# matrix_4x4.net
KiCad netlist of a schematic drawn in EAGLE
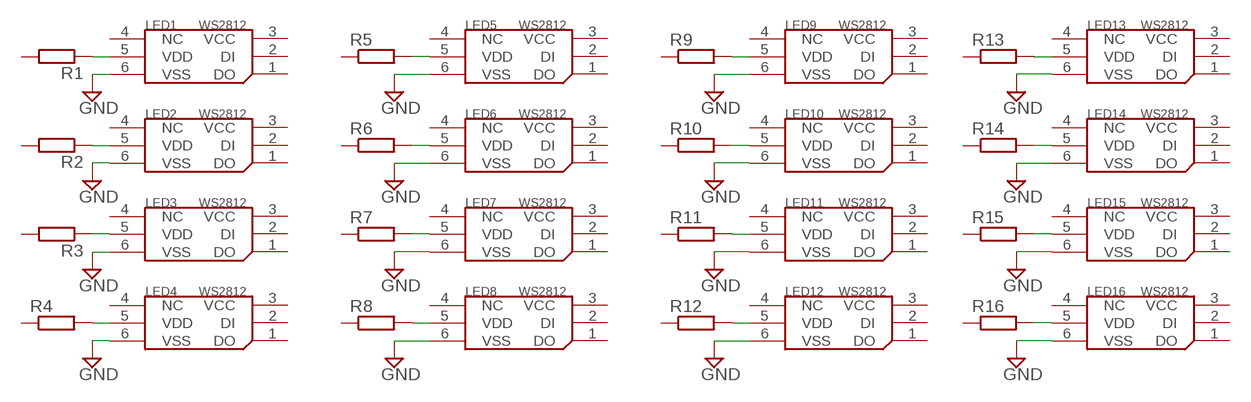
[diagram p0: schematic, sheet 1]

(export (version "E")
  (design (tool "Eeschema 10.0.6"))
  (components
    (comp (ref "LED1")
      (value "WS2812")
      (footprint "eagle-import:LED6-SMD-5050")
      (libsource (lib "eagle-import") (part "WS2812"))
    )
    (comp (ref "LED2")
      (value "WS2812")
      (footprint "eagle-import:LED6-SMD-5050")
      (libsource (lib "eagle-import") (part "WS2812"))
    )
    (comp (ref "LED3")
      (value "WS2812")
      (footprint "eagle-import:LED6-SMD-5050")
      (libsource (lib "eagle-import") (part "WS2812"))
    )
    (comp (ref "LED4")
      (value "WS2812")
      (footprint "eagle-import:LED6-SMD-5050")
      (libsource (lib "eagle-import") (part "WS2812"))
    )
    (comp (ref "LED5")
      (value "WS2812")
      (footprint "eagle-import:LED6-SMD-5050")
      (libsource (lib "eagle-import") (part "WS2812"))
    )
    (comp (ref "LED6")
      (value "WS2812")
      (footprint "eagle-import:LED6-SMD-5050")
      (libsource (lib "eagle-import") (part "WS2812"))
    )
    (comp (ref "LED7")
      (value "WS2812")
      (footprint "eagle-import:LED6-SMD-5050")
      (libsource (lib "eagle-import") (part "WS2812"))
    )
    (comp (ref "LED8")
      (value "WS2812")
      (footprint "eagle-import:LED6-SMD-5050")
      (libsource (lib "eagle-import") (part "WS2812"))
    )
    (comp (ref "LED9")
      (value "WS2812")
      (footprint "eagle-import:LED6-SMD-5050")
      (libsource (lib "eagle-import") (part "WS2812"))
    )
    (comp (ref "LED10")
      (value "WS2812")
      (footprint "eagle-import:LED6-SMD-5050")
      (libsource (lib "eagle-import") (part "WS2812"))
    )
    (comp (ref "LED11")
      (value "WS2812")
      (footprint "eagle-import:LED6-SMD-5050")
      (libsource (lib "eagle-import") (part "WS2812"))
    )
    (comp (ref "LED12")
      (value "WS2812")
      (footprint "eagle-import:LED6-SMD-5050")
      (libsource (lib "eagle-import") (part "WS2812"))
    )
    (comp (ref "LED13")
      (value "WS2812")
      (footprint "eagle-import:LED6-SMD-5050")
      (libsource (lib "eagle-import") (part "WS2812"))
    )
    (comp (ref "LED14")
      (value "WS2812")
      (footprint "eagle-import:LED6-SMD-5050")
      (libsource (lib "eagle-import") (part "WS2812"))
    )
    (comp (ref "LED15")
      (value "WS2812")
      (footprint "eagle-import:LED6-SMD-5050")
      (libsource (lib "eagle-import") (part "WS2812"))
    )
    (comp (ref "LED16")
      (value "WS2812")
      (footprint "eagle-import:LED6-SMD-5050")
      (libsource (lib "eagle-import") (part "WS2812"))
    )
    (comp (ref "R1")
      (value "R-EU_M0805")
      (footprint "eagle-import:M0805")
      (libsource (lib "eagle-import") (part "R-EU_M0805"))
    )
    (comp (ref "R2")
      (value "R-EU_M0805")
      (footprint "eagle-import:M0805")
      (libsource (lib "eagle-import") (part "R-EU_M0805"))
    )
    (comp (ref "R3")
      (value "R-EU_M0805")
      (footprint "eagle-import:M0805")
      (libsource (lib "eagle-import") (part "R-EU_M0805"))
    )
    (comp (ref "R4")
      (value "R-EU_M0805")
      (footprint "eagle-import:M0805")
      (libsource (lib "eagle-import") (part "R-EU_M0805"))
    )
    (comp (ref "R5")
      (value "R-EU_M0805")
      (footprint "eagle-import:M0805")
      (libsource (lib "eagle-import") (part "R-EU_M0805"))
    )
    (comp (ref "R6")
      (value "R-EU_M0805")
      (footprint "eagle-import:M0805")
      (libsource (lib "eagle-import") (part "R-EU_M0805"))
    )
    (comp (ref "R7")
      (value "R-EU_M0805")
      (footprint "eagle-import:M0805")
      (libsource (lib "eagle-import") (part "R-EU_M0805"))
    )
    (comp (ref "R8")
      (value "R-EU_M0805")
      (footprint "eagle-import:M0805")
      (libsource (lib "eagle-import") (part "R-EU_M0805"))
    )
    (comp (ref "R9")
      (value "R-EU_M0805")
      (footprint "eagle-import:M0805")
      (libsource (lib "eagle-import") (part "R-EU_M0805"))
    )
    (comp (ref "R10")
      (value "R-EU_M0805")
      (footprint "eagle-import:M0805")
      (libsource (lib "eagle-import") (part "R-EU_M0805"))
    )
    (comp (ref "R11")
      (value "R-EU_M0805")
      (footprint "eagle-import:M0805")
      (libsource (lib "eagle-import") (part "R-EU_M0805"))
    )
    (comp (ref "R12")
      (value "R-EU_M0805")
      (footprint "eagle-import:M0805")
      (libsource (lib "eagle-import") (part "R-EU_M0805"))
    )
    (comp (ref "R13")
      (value "R-EU_M0805")
      (footprint "eagle-import:M0805")
      (libsource (lib "eagle-import") (part "R-EU_M0805"))
    )
    (comp (ref "R14")
      (value "R-EU_M0805")
      (footprint "eagle-import:M0805")
      (libsource (lib "eagle-import") (part "R-EU_M0805"))
    )
    (comp (ref "R15")
      (value "R-EU_M0805")
      (footprint "eagle-import:M0805")
      (libsource (lib "eagle-import") (part "R-EU_M0805"))
    )
    (comp (ref "R16")
      (value "R-EU_M0805")
      (footprint "eagle-import:M0805")
      (libsource (lib "eagle-import") (part "R-EU_M0805"))
    )
  )
  (nets
    (net (code "1") (name "GND") (class "Default")
      (node (ref "LED1") (pin "6") (pinfunction "VSS_6") (pintype "bidirectional"))
      (node (ref "LED10") (pin "6") (pinfunction "VSS_6") (pintype "bidirectional"))
      (node (ref "LED11") (pin "6") (pinfunction "VSS_6") (pintype "bidirectional"))
      (node (ref "LED12") (pin "6") (pinfunction "VSS_6") (pintype "bidirectional"))
      (node (ref "LED13") (pin "6") (pinfunction "VSS_6") (pintype "bidirectional"))
      (node (ref "LED14") (pin "6") (pinfunction "VSS_6") (pintype "bidirectional"))
      (node (ref "LED15") (pin "6") (pinfunction "VSS_6") (pintype "bidirectional"))
      (node (ref "LED16") (pin "6") (pinfunction "VSS_6") (pintype "bidirectional"))
      (node (ref "LED2") (pin "6") (pinfunction "VSS_6") (pintype "bidirectional"))
      (node (ref "LED3") (pin "6") (pinfunction "VSS_6") (pintype "bidirectional"))
      (node (ref "LED4") (pin "6") (pinfunction "VSS_6") (pintype "bidirectional"))
      (node (ref "LED5") (pin "6") (pinfunction "VSS_6") (pintype "bidirectional"))
      (node (ref "LED6") (pin "6") (pinfunction "VSS_6") (pintype "bidirectional"))
      (node (ref "LED7") (pin "6") (pinfunction "VSS_6") (pintype "bidirectional"))
      (node (ref "LED8") (pin "6") (pinfunction "VSS_6") (pintype "bidirectional"))
      (node (ref "LED9") (pin "6") (pinfunction "VSS_6") (pintype "bidirectional"))
    )
    (net (code "2") (name "Net-(LED1-VDD)") (class "Default")
      (node (ref "LED1") (pin "5") (pinfunction "VDD_5") (pintype "bidirectional"))
      (node (ref "R1") (pin "1") (pinfunction "1_1") (pintype "passive"))
    )
    (net (code "3") (name "Net-(LED2-VDD)") (class "Default")
      (node (ref "LED2") (pin "5") (pinfunction "VDD_5") (pintype "bidirectional"))
      (node (ref "R2") (pin "1") (pinfunction "1_1") (pintype "passive"))
    )
    (net (code "4") (name "Net-(LED3-VDD)") (class "Default")
      (node (ref "LED3") (pin "5") (pinfunction "VDD_5") (pintype "bidirectional"))
      (node (ref "R3") (pin "1") (pinfunction "1_1") (pintype "passive"))
    )
    (net (code "5") (name "Net-(LED4-VDD)") (class "Default")
      (node (ref "LED4") (pin "5") (pinfunction "VDD_5") (pintype "bidirectional"))
      (node (ref "R4") (pin "2") (pinfunction "2_2") (pintype "passive"))
    )
    (net (code "6") (name "Net-(LED5-VDD)") (class "Default")
      (node (ref "LED5") (pin "5") (pinfunction "VDD_5") (pintype "bidirectional"))
      (node (ref "R5") (pin "2") (pinfunction "2_2") (pintype "passive"))
    )
    (net (code "7") (name "Net-(LED6-VDD)") (class "Default")
      (node (ref "LED6") (pin "5") (pinfunction "VDD_5") (pintype "bidirectional"))
      (node (ref "R6") (pin "2") (pinfunction "2_2") (pintype "passive"))
    )
    (net (code "8") (name "Net-(LED7-VDD)") (class "Default")
      (node (ref "LED7") (pin "5") (pinfunction "VDD_5") (pintype "bidirectional"))
      (node (ref "R7") (pin "2") (pinfunction "2_2") (pintype "passive"))
    )
    (net (code "9") (name "Net-(LED8-VDD)") (class "Default")
      (node (ref "LED8") (pin "5") (pinfunction "VDD_5") (pintype "bidirectional"))
      (node (ref "R8") (pin "2") (pinfunction "2_2") (pintype "passive"))
    )
    (net (code "10") (name "Net-(LED9-VDD)") (class "Default")
      (node (ref "LED9") (pin "5") (pinfunction "VDD_5") (pintype "bidirectional"))
      (node (ref "R9") (pin "2") (pinfunction "2_2") (pintype "passive"))
    )
    (net (code "11") (name "Net-(LED10-VDD)") (class "Default")
      (node (ref "LED10") (pin "5") (pinfunction "VDD_5") (pintype "bidirectional"))
      (node (ref "R10") (pin "2") (pinfunction "2_2") (pintype "passive"))
    )
    (net (code "12") (name "Net-(LED11-VDD)") (class "Default")
      (node (ref "LED11") (pin "5") (pinfunction "VDD_5") (pintype "bidirectional"))
      (node (ref "R11") (pin "2") (pinfunction "2_2") (pintype "passive"))
    )
    (net (code "13") (name "Net-(LED12-VDD)") (class "Default")
      (node (ref "LED12") (pin "5") (pinfunction "VDD_5") (pintype "bidirectional"))
      (node (ref "R12") (pin "2") (pinfunction "2_2") (pintype "passive"))
    )
    (net (code "14") (name "Net-(LED13-VDD)") (class "Default")
      (node (ref "LED13") (pin "5") (pinfunction "VDD_5") (pintype "bidirectional"))
      (node (ref "R13") (pin "2") (pinfunction "2_2") (pintype "passive"))
    )
    (net (code "15") (name "Net-(LED14-VDD)") (class "Default")
      (node (ref "LED14") (pin "5") (pinfunction "VDD_5") (pintype "bidirectional"))
      (node (ref "R14") (pin "2") (pinfunction "2_2") (pintype "passive"))
    )
    (net (code "16") (name "Net-(LED15-VDD)") (class "Default")
      (node (ref "LED15") (pin "5") (pinfunction "VDD_5") (pintype "bidirectional"))
      (node (ref "R15") (pin "2") (pinfunction "2_2") (pintype "passive"))
    )
    (net (code "17") (name "Net-(LED16-VDD)") (class "Default")
      (node (ref "LED16") (pin "5") (pinfunction "VDD_5") (pintype "bidirectional"))
      (node (ref "R16") (pin "2") (pinfunction "2_2") (pintype "passive"))
    )
    (net (code "18") (name "unconnected-(LED1-DI-Pad2)") (class "Default")
      (node (ref "LED1") (pin "2") (pinfunction "DI_2") (pintype "bidirectional"))
    )
    (net (code "19") (name "unconnected-(LED1-DO-Pad1)") (class "Default")
      (node (ref "LED1") (pin "1") (pinfunction "DO_1") (pintype "bidirectional"))
    )
    (net (code "20") (name "unconnected-(LED1-NC-Pad4)") (class "Default")
      (node (ref "LED1") (pin "4") (pinfunction "NC_4") (pintype "bidirectional"))
    )
    (net (code "21") (name "unconnected-(LED1-VCC-Pad3)") (class "Default")
      (node (ref "LED1") (pin "3") (pinfunction "VCC_3") (pintype "bidirectional"))
    )
    (net (code "22") (name "unconnected-(LED2-DI-Pad2)") (class "Default")
      (node (ref "LED2") (pin "2") (pinfunction "DI_2") (pintype "bidirectional"))
    )
    (net (code "23") (name "unconnected-(LED2-DO-Pad1)") (class "Default")
      (node (ref "LED2") (pin "1") (pinfunction "DO_1") (pintype "bidirectional"))
    )
    (net (code "24") (name "unconnected-(LED2-NC-Pad4)") (class "Default")
      (node (ref "LED2") (pin "4") (pinfunction "NC_4") (pintype "bidirectional"))
    )
    (net (code "25") (name "unconnected-(LED2-VCC-Pad3)") (class "Default")
      (node (ref "LED2") (pin "3") (pinfunction "VCC_3") (pintype "bidirectional"))
    )
    (net (code "26") (name "unconnected-(LED3-DI-Pad2)") (class "Default")
      (node (ref "LED3") (pin "2") (pinfunction "DI_2") (pintype "bidirectional"))
    )
    (net (code "27") (name "unconnected-(LED3-DO-Pad1)") (class "Default")
      (node (ref "LED3") (pin "1") (pinfunction "DO_1") (pintype "bidirectional"))
    )
    (net (code "28") (name "unconnected-(LED3-NC-Pad4)") (class "Default")
      (node (ref "LED3") (pin "4") (pinfunction "NC_4") (pintype "bidirectional"))
    )
    (net (code "29") (name "unconnected-(LED3-VCC-Pad3)") (class "Default")
      (node (ref "LED3") (pin "3") (pinfunction "VCC_3") (pintype "bidirectional"))
    )
    (net (code "30") (name "unconnected-(LED4-DI-Pad2)") (class "Default")
      (node (ref "LED4") (pin "2") (pinfunction "DI_2") (pintype "bidirectional"))
    )
    (net (code "31") (name "unconnected-(LED4-DO-Pad1)") (class "Default")
      (node (ref "LED4") (pin "1") (pinfunction "DO_1") (pintype "bidirectional"))
    )
    (net (code "32") (name "unconnected-(LED4-NC-Pad4)") (class "Default")
      (node (ref "LED4") (pin "4") (pinfunction "NC_4") (pintype "bidirectional"))
    )
    (net (code "33") (name "unconnected-(LED4-VCC-Pad3)") (class "Default")
      (node (ref "LED4") (pin "3") (pinfunction "VCC_3") (pintype "bidirectional"))
    )
    (net (code "34") (name "unconnected-(LED5-DI-Pad2)") (class "Default")
      (node (ref "LED5") (pin "2") (pinfunction "DI_2") (pintype "bidirectional"))
    )
    (net (code "35") (name "unconnected-(LED5-DO-Pad1)") (class "Default")
      (node (ref "LED5") (pin "1") (pinfunction "DO_1") (pintype "bidirectional"))
    )
    (net (code "36") (name "unconnected-(LED5-NC-Pad4)") (class "Default")
      (node (ref "LED5") (pin "4") (pinfunction "NC_4") (pintype "bidirectional"))
    )
    (net (code "37") (name "unconnected-(LED5-VCC-Pad3)") (class "Default")
      (node (ref "LED5") (pin "3") (pinfunction "VCC_3") (pintype "bidirectional"))
    )
    (net (code "38") (name "unconnected-(LED6-DI-Pad2)") (class "Default")
      (node (ref "LED6") (pin "2") (pinfunction "DI_2") (pintype "bidirectional"))
    )
    (net (code "39") (name "unconnected-(LED6-DO-Pad1)") (class "Default")
      (node (ref "LED6") (pin "1") (pinfunction "DO_1") (pintype "bidirectional"))
    )
    (net (code "40") (name "unconnected-(LED6-NC-Pad4)") (class "Default")
      (node (ref "LED6") (pin "4") (pinfunction "NC_4") (pintype "bidirectional"))
    )
    (net (code "41") (name "unconnected-(LED6-VCC-Pad3)") (class "Default")
      (node (ref "LED6") (pin "3") (pinfunction "VCC_3") (pintype "bidirectional"))
    )
    (net (code "42") (name "unconnected-(LED7-DI-Pad2)") (class "Default")
      (node (ref "LED7") (pin "2") (pinfunction "DI_2") (pintype "bidirectional"))
    )
    (net (code "43") (name "unconnected-(LED7-DO-Pad1)") (class "Default")
      (node (ref "LED7") (pin "1") (pinfunction "DO_1") (pintype "bidirectional"))
    )
    (net (code "44") (name "unconnected-(LED7-NC-Pad4)") (class "Default")
      (node (ref "LED7") (pin "4") (pinfunction "NC_4") (pintype "bidirectional"))
    )
    (net (code "45") (name "unconnected-(LED7-VCC-Pad3)") (class "Default")
      (node (ref "LED7") (pin "3") (pinfunction "VCC_3") (pintype "bidirectional"))
    )
    (net (code "46") (name "unconnected-(LED8-DI-Pad2)") (class "Default")
      (node (ref "LED8") (pin "2") (pinfunction "DI_2") (pintype "bidirectional"))
    )
    (net (code "47") (name "unconnected-(LED8-DO-Pad1)") (class "Default")
      (node (ref "LED8") (pin "1") (pinfunction "DO_1") (pintype "bidirectional"))
    )
    (net (code "48") (name "unconnected-(LED8-NC-Pad4)") (class "Default")
      (node (ref "LED8") (pin "4") (pinfunction "NC_4") (pintype "bidirectional"))
    )
    (net (code "49") (name "unconnected-(LED8-VCC-Pad3)") (class "Default")
      (node (ref "LED8") (pin "3") (pinfunction "VCC_3") (pintype "bidirectional"))
    )
    (net (code "50") (name "unconnected-(LED9-DI-Pad2)") (class "Default")
      (node (ref "LED9") (pin "2") (pinfunction "DI_2") (pintype "bidirectional"))
    )
    (net (code "51") (name "unconnected-(LED9-DO-Pad1)") (class "Default")
      (node (ref "LED9") (pin "1") (pinfunction "DO_1") (pintype "bidirectional"))
    )
    (net (code "52") (name "unconnected-(LED9-NC-Pad4)") (class "Default")
      (node (ref "LED9") (pin "4") (pinfunction "NC_4") (pintype "bidirectional"))
    )
    (net (code "53") (name "unconnected-(LED9-VCC-Pad3)") (class "Default")
      (node (ref "LED9") (pin "3") (pinfunction "VCC_3") (pintype "bidirectional"))
    )
    (net (code "54") (name "unconnected-(LED10-DI-Pad2)") (class "Default")
      (node (ref "LED10") (pin "2") (pinfunction "DI_2") (pintype "bidirectional"))
    )
    (net (code "55") (name "unconnected-(LED10-DO-Pad1)") (class "Default")
      (node (ref "LED10") (pin "1") (pinfunction "DO_1") (pintype "bidirectional"))
    )
    (net (code "56") (name "unconnected-(LED10-NC-Pad4)") (class "Default")
      (node (ref "LED10") (pin "4") (pinfunction "NC_4") (pintype "bidirectional"))
    )
    (net (code "57") (name "unconnected-(LED10-VCC-Pad3)") (class "Default")
      (node (ref "LED10") (pin "3") (pinfunction "VCC_3") (pintype "bidirectional"))
    )
    (net (code "58") (name "unconnected-(LED11-DI-Pad2)") (class "Default")
      (node (ref "LED11") (pin "2") (pinfunction "DI_2") (pintype "bidirectional"))
    )
    (net (code "59") (name "unconnected-(LED11-DO-Pad1)") (class "Default")
      (node (ref "LED11") (pin "1") (pinfunction "DO_1") (pintype "bidirectional"))
    )
    (net (code "60") (name "unconnected-(LED11-NC-Pad4)") (class "Default")
      (node (ref "LED11") (pin "4") (pinfunction "NC_4") (pintype "bidirectional"))
    )
    (net (code "61") (name "unconnected-(LED11-VCC-Pad3)") (class "Default")
      (node (ref "LED11") (pin "3") (pinfunction "VCC_3") (pintype "bidirectional"))
    )
    (net (code "62") (name "unconnected-(LED12-DI-Pad2)") (class "Default")
      (node (ref "LED12") (pin "2") (pinfunction "DI_2") (pintype "bidirectional"))
    )
    (net (code "63") (name "unconnected-(LED12-DO-Pad1)") (class "Default")
      (node (ref "LED12") (pin "1") (pinfunction "DO_1") (pintype "bidirectional"))
    )
    (net (code "64") (name "unconnected-(LED12-NC-Pad4)") (class "Default")
      (node (ref "LED12") (pin "4") (pinfunction "NC_4") (pintype "bidirectional"))
    )
    (net (code "65") (name "unconnected-(LED12-VCC-Pad3)") (class "Default")
      (node (ref "LED12") (pin "3") (pinfunction "VCC_3") (pintype "bidirectional"))
    )
    (net (code "66") (name "unconnected-(LED13-DI-Pad2)") (class "Default")
      (node (ref "LED13") (pin "2") (pinfunction "DI_2") (pintype "bidirectional"))
    )
    (net (code "67") (name "unconnected-(LED13-DO-Pad1)") (class "Default")
      (node (ref "LED13") (pin "1") (pinfunction "DO_1") (pintype "bidirectional"))
    )
    (net (code "68") (name "unconnected-(LED13-NC-Pad4)") (class "Default")
      (node (ref "LED13") (pin "4") (pinfunction "NC_4") (pintype "bidirectional"))
    )
    (net (code "69") (name "unconnected-(LED13-VCC-Pad3)") (class "Default")
      (node (ref "LED13") (pin "3") (pinfunction "VCC_3") (pintype "bidirectional"))
    )
    (net (code "70") (name "unconnected-(LED14-DI-Pad2)") (class "Default")
      (node (ref "LED14") (pin "2") (pinfunction "DI_2") (pintype "bidirectional"))
    )
    (net (code "71") (name "unconnected-(LED14-DO-Pad1)") (class "Default")
      (node (ref "LED14") (pin "1") (pinfunction "DO_1") (pintype "bidirectional"))
    )
    (net (code "72") (name "unconnected-(LED14-NC-Pad4)") (class "Default")
      (node (ref "LED14") (pin "4") (pinfunction "NC_4") (pintype "bidirectional"))
    )
    (net (code "73") (name "unconnected-(LED14-VCC-Pad3)") (class "Default")
      (node (ref "LED14") (pin "3") (pinfunction "VCC_3") (pintype "bidirectional"))
    )
    (net (code "74") (name "unconnected-(LED15-DI-Pad2)") (class "Default")
      (node (ref "LED15") (pin "2") (pinfunction "DI_2") (pintype "bidirectional"))
    )
    (net (code "75") (name "unconnected-(LED15-DO-Pad1)") (class "Default")
      (node (ref "LED15") (pin "1") (pinfunction "DO_1") (pintype "bidirectional"))
    )
    (net (code "76") (name "unconnected-(LED15-NC-Pad4)") (class "Default")
      (node (ref "LED15") (pin "4") (pinfunction "NC_4") (pintype "bidirectional"))
    )
    (net (code "77") (name "unconnected-(LED15-VCC-Pad3)") (class "Default")
      (node (ref "LED15") (pin "3") (pinfunction "VCC_3") (pintype "bidirectional"))
    )
    (net (code "78") (name "unconnected-(LED16-DI-Pad2)") (class "Default")
      (node (ref "LED16") (pin "2") (pinfunction "DI_2") (pintype "bidirectional"))
    )
    (net (code "79") (name "unconnected-(LED16-DO-Pad1)") (class "Default")
      (node (ref "LED16") (pin "1") (pinfunction "DO_1") (pintype "bidirectional"))
    )
    (net (code "80") (name "unconnected-(LED16-NC-Pad4)") (class "Default")
      (node (ref "LED16") (pin "4") (pinfunction "NC_4") (pintype "bidirectional"))
    )
    (net (code "81") (name "unconnected-(LED16-VCC-Pad3)") (class "Default")
      (node (ref "LED16") (pin "3") (pinfunction "VCC_3") (pintype "bidirectional"))
    )
    (net (code "82") (name "unconnected-(R1-Pad2)") (class "Default")
      (node (ref "R1") (pin "2") (pinfunction "2_2") (pintype "passive"))
    )
    (net (code "83") (name "unconnected-(R2-Pad2)") (class "Default")
      (node (ref "R2") (pin "2") (pinfunction "2_2") (pintype "passive"))
    )
    (net (code "84") (name "unconnected-(R3-Pad2)") (class "Default")
      (node (ref "R3") (pin "2") (pinfunction "2_2") (pintype "passive"))
    )
    (net (code "85") (name "unconnected-(R4-Pad1)") (class "Default")
      (node (ref "R4") (pin "1") (pinfunction "1_1") (pintype "passive"))
    )
    (net (code "86") (name "unconnected-(R5-Pad1)") (class "Default")
      (node (ref "R5") (pin "1") (pinfunction "1_1") (pintype "passive"))
    )
    (net (code "87") (name "unconnected-(R6-Pad1)") (class "Default")
      (node (ref "R6") (pin "1") (pinfunction "1_1") (pintype "passive"))
    )
    (net (code "88") (name "unconnected-(R7-Pad1)") (class "Default")
      (node (ref "R7") (pin "1") (pinfunction "1_1") (pintype "passive"))
    )
    (net (code "89") (name "unconnected-(R8-Pad1)") (class "Default")
      (node (ref "R8") (pin "1") (pinfunction "1_1") (pintype "passive"))
    )
    (net (code "90") (name "unconnected-(R9-Pad1)") (class "Default")
      (node (ref "R9") (pin "1") (pinfunction "1_1") (pintype "passive"))
    )
    (net (code "91") (name "unconnected-(R10-Pad1)") (class "Default")
      (node (ref "R10") (pin "1") (pinfunction "1_1") (pintype "passive"))
    )
    (net (code "92") (name "unconnected-(R11-Pad1)") (class "Default")
      (node (ref "R11") (pin "1") (pinfunction "1_1") (pintype "passive"))
    )
    (net (code "93") (name "unconnected-(R12-Pad1)") (class "Default")
      (node (ref "R12") (pin "1") (pinfunction "1_1") (pintype "passive"))
    )
    (net (code "94") (name "unconnected-(R13-Pad1)") (class "Default")
      (node (ref "R13") (pin "1") (pinfunction "1_1") (pintype "passive"))
    )
    (net (code "95") (name "unconnected-(R14-Pad1)") (class "Default")
      (node (ref "R14") (pin "1") (pinfunction "1_1") (pintype "passive"))
    )
    (net (code "96") (name "unconnected-(R15-Pad1)") (class "Default")
      (node (ref "R15") (pin "1") (pinfunction "1_1") (pintype "passive"))
    )
    (net (code "97") (name "unconnected-(R16-Pad1)") (class "Default")
      (node (ref "R16") (pin "1") (pinfunction "1_1") (pintype "passive"))
    )
  )
)
